# lab10.net
KiCad netlist of a schematic drawn in EAGLE
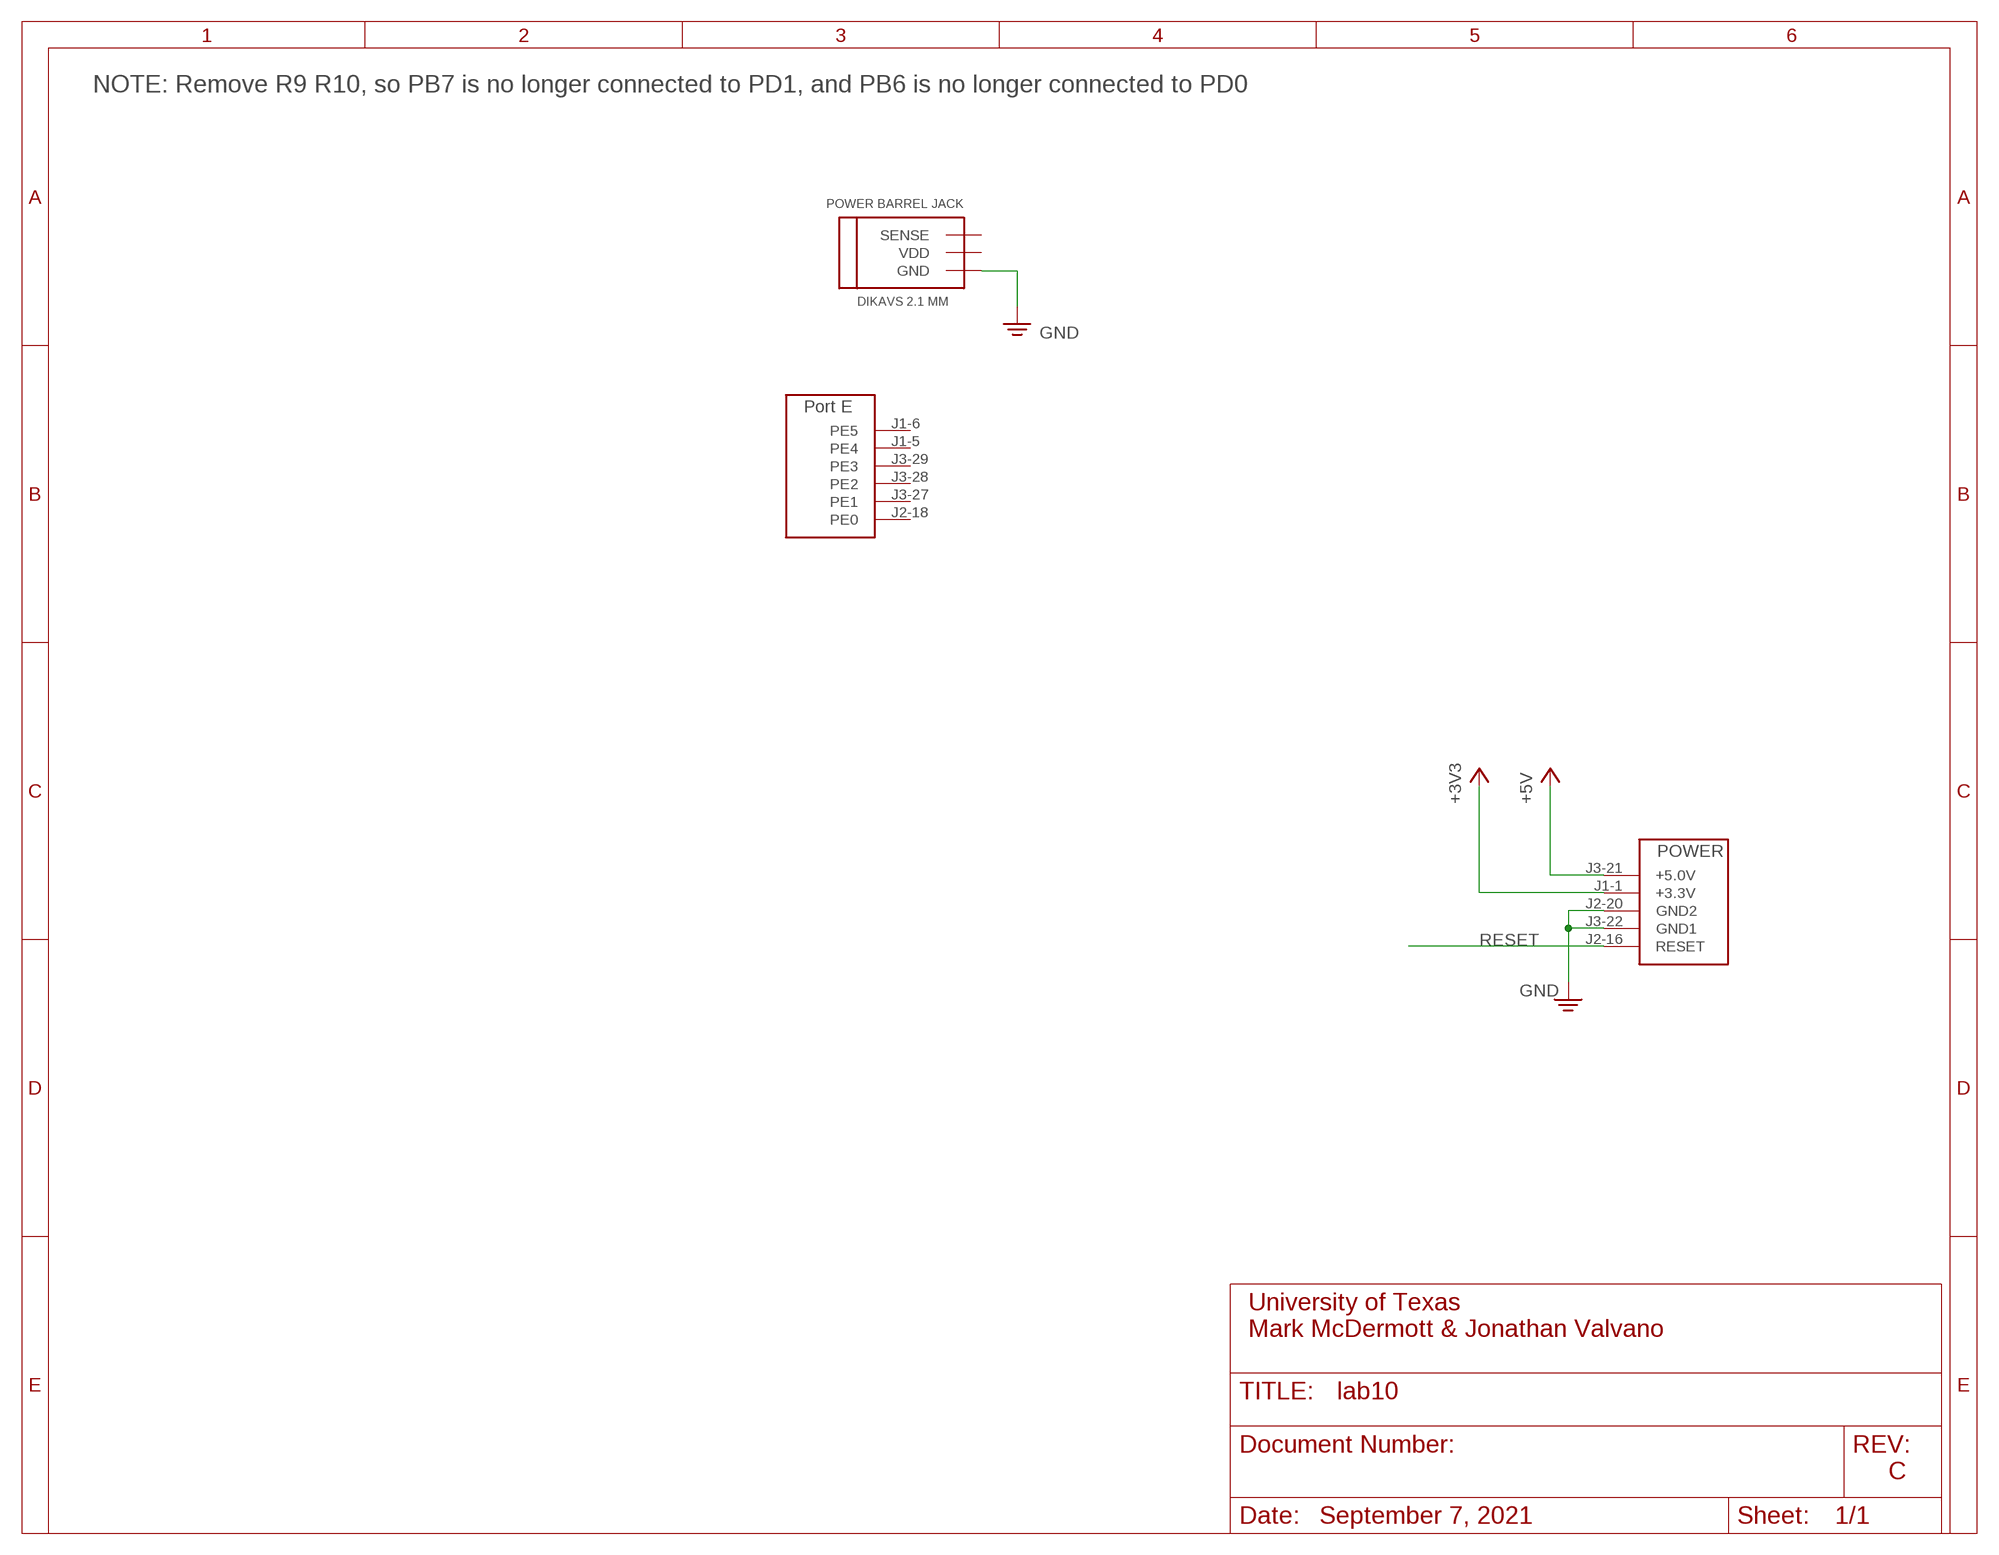
[diagram p0: schematic, sheet 1, part 1 of 2]
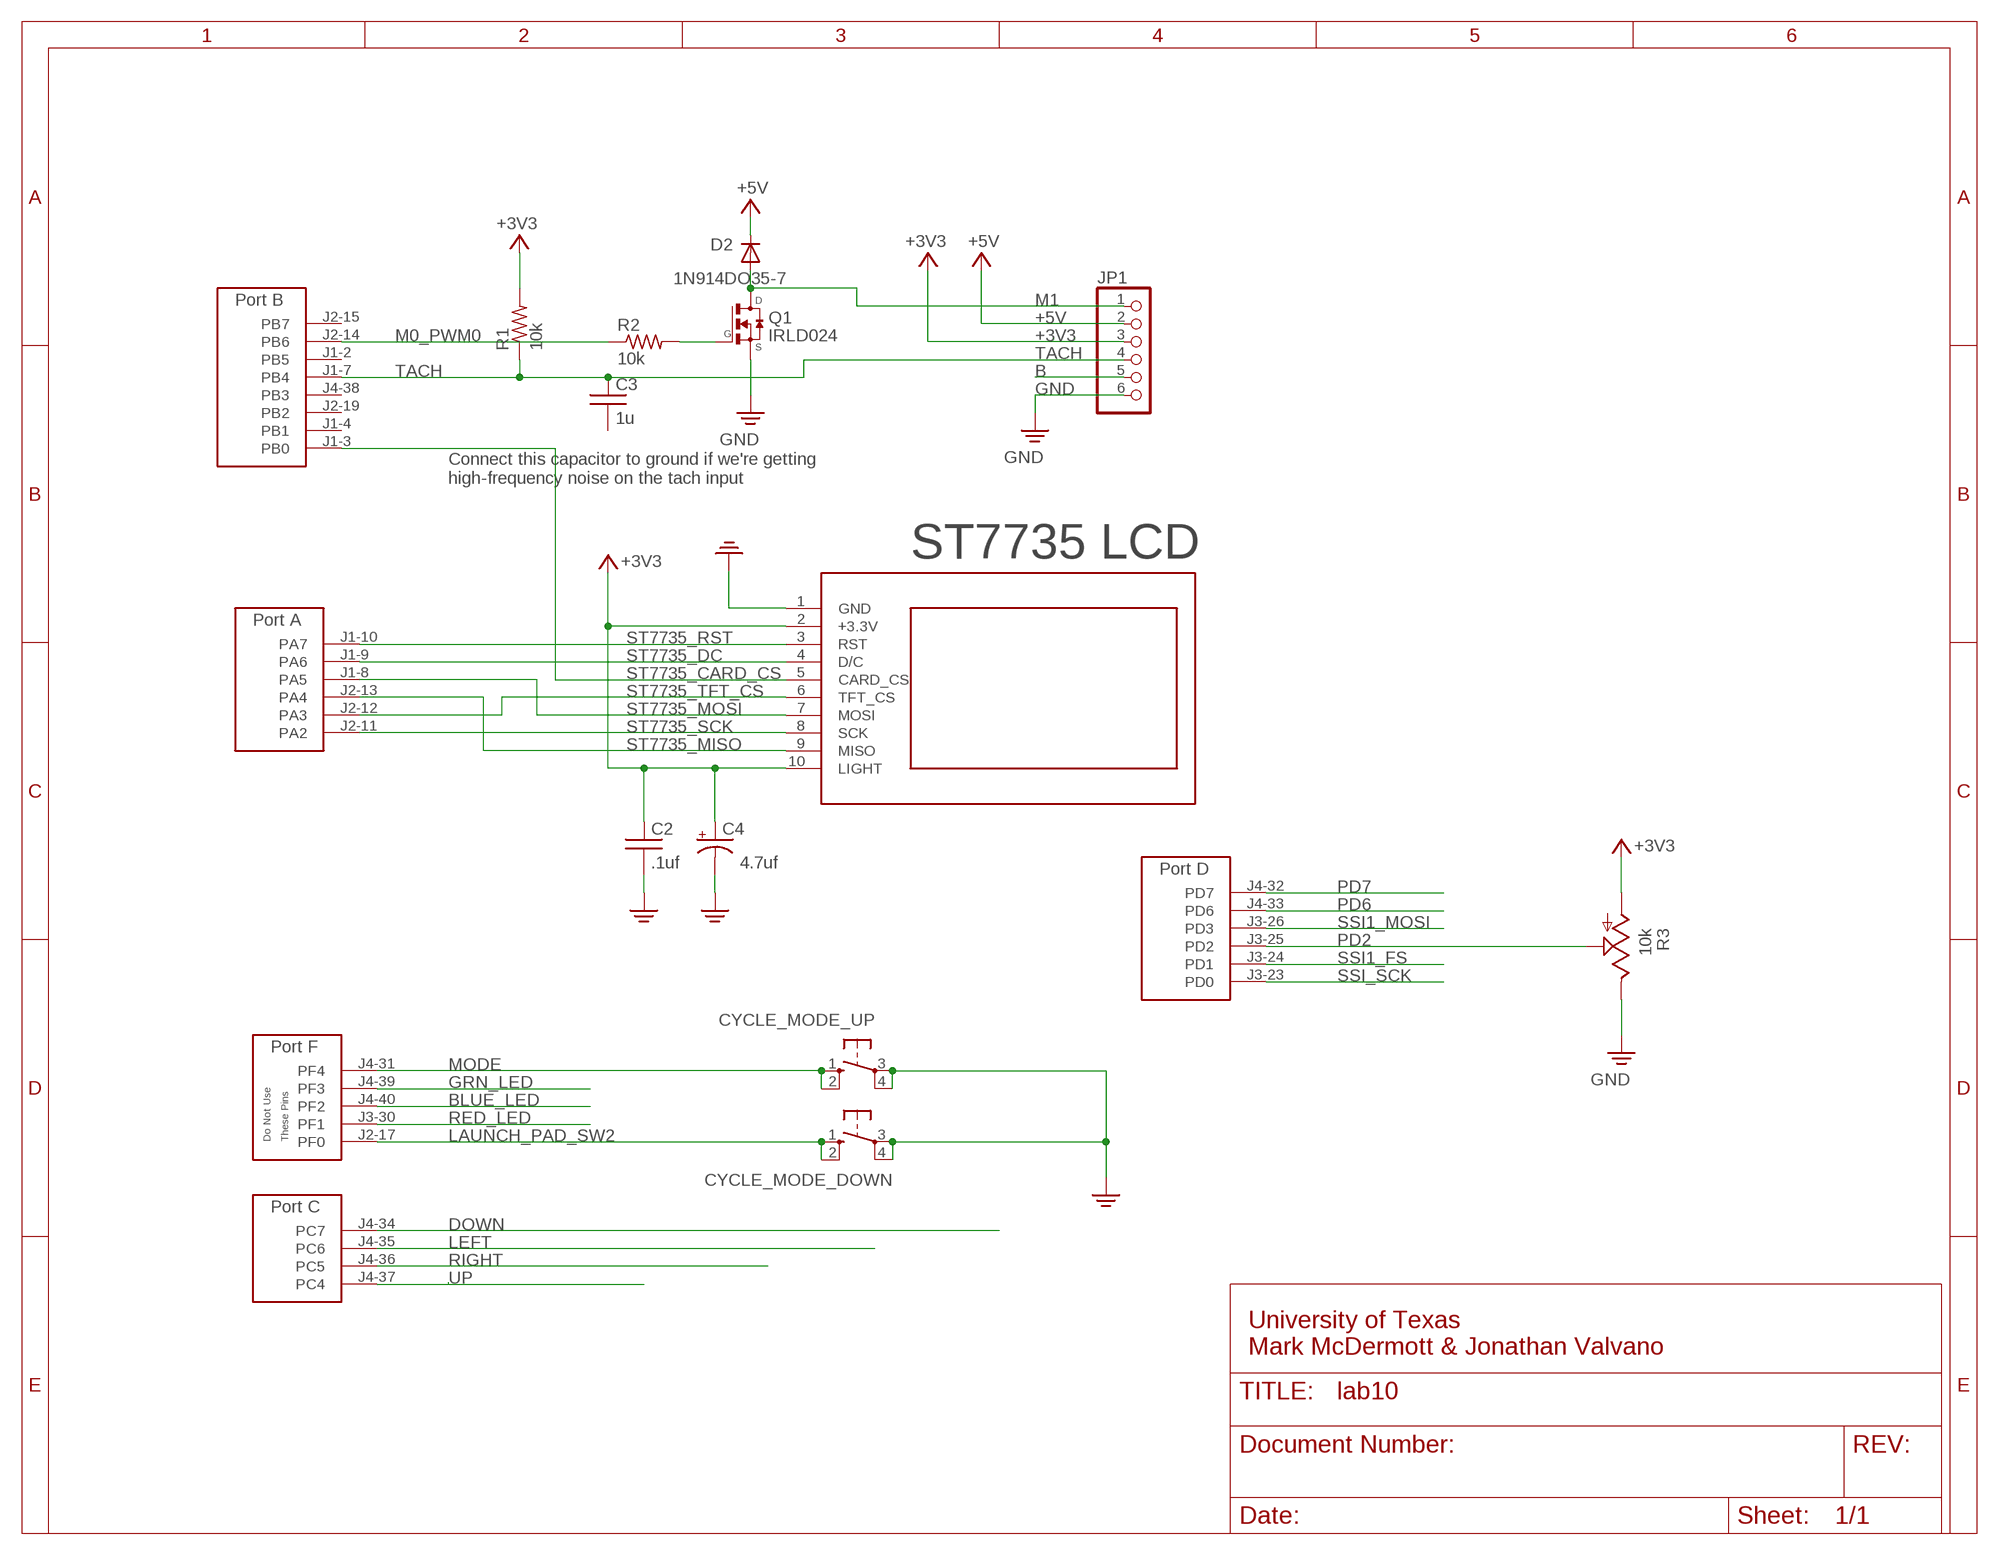
[diagram p1: schematic, sheet 1, part 2 of 2]

(export (version "E")
  (design (tool "Eeschema 10.0.6"))
  (components
    (comp (ref "C2")
      (value ".1uf")
      (footprint "eagle-import:CAP200MIL")
      (libsource (lib "eagle-import") (part "CAPACITOR050-024X044"))
    )
    (comp (ref "C3")
      (value "1u")
      (footprint "eagle-import:CAP100MIL")
      (libsource (lib "eagle-import") (part "EE445L_31078833_CAPACITOR025-024X044"))
    )
    (comp (ref "C4")
      (value "4.7uf")
      (footprint "eagle-import:CAP200MILPOLARIZED")
      (libsource (lib "eagle-import") (part "CAPACITOR_POLARIZEDE5-6"))
    )
    (comp (ref "CYCLE_MODE_DOWN")
      (value "B3F-1052")
      (footprint "eagle-import:B3F-10XX")
      (fields (field (name "MPN") "B3F-1000"))
      (libsource (lib "eagle-import") (part "B3F-1052"))
    )
    (comp (ref "CYCLE_MODE_UP")
      (value "B3F-1052")
      (footprint "eagle-import:B3F-10XX")
      (fields (field (name "MPN") "B3F-1000"))
      (libsource (lib "eagle-import") (part "B3F-1052"))
    )
    (comp (ref "D2")
      (value "1N914DO35-7")
      (footprint "eagle-import:DO35-7")
      (libsource (lib "eagle-import") (part "1N914DO35-7"))
    )
    (comp (ref "JP1")
      (value "PINHD-1X6")
      (footprint "eagle-import:1X06")
      (libsource (lib "eagle-import") (part "PINHD-1X6"))
    )
    (comp (ref "Q1")
      (value "IRLD024")
      (footprint "eagle-import:IRLD024")
      (libsource (lib "eagle-import") (part "IRLD024"))
    )
    (comp (ref "R1")
      (value "10k")
      (footprint "eagle-import:RES300MIL")
      (libsource (lib "eagle-import") (part "RESISTOR0204/7"))
    )
    (comp (ref "R2")
      (value "10k")
      (footprint "eagle-import:RES300MIL")
      (libsource (lib "eagle-import") (part "RESISTOR0204/7"))
    )
    (comp (ref "R3")
      (value "10k")
      (footprint "eagle-import:PTA2043")
      (libsource (lib "eagle-import") (part "POTENTIOMETER_PTA2043B25U"))
    )
    (comp (ref "U$2")
      (value "TM4C_BP")
      (footprint "eagle-import:TM4C_BOOSTER_PACK")
      (libsource (lib "eagle-import") (part "TM4C_BP"))
    )
    (comp (ref "U$3")
      (value "ST7735")
      (footprint "eagle-import:ST7735")
      (libsource (lib "eagle-import") (part "ST7735"))
    )
    (comp (ref "U$4")
      (value "2.1MM_BARREL_JACK")
      (footprint "eagle-import:2.1M_BARREL_JACK")
      (libsource (lib "eagle-import") (part "2.1MM_BARREL_JACK"))
    )
  )
  (nets
    (net (code "1") (name "+3V3") (class "Default")
      (node (ref "C2") (pin "1") (pinfunction "1_1") (pintype "passive"))
      (node (ref "C4") (pin "+") (pinfunction "+_+") (pintype "passive"))
      (node (ref "JP1") (pin "3") (pinfunction "3_3") (pintype "passive"))
      (node (ref "R1") (pin "2") (pinfunction "2_2") (pintype "passive"))
      (node (ref "R3") (pin "3") (pinfunction "A_3") (pintype "passive"))
      (node (ref "U$2") (pin "J1-1") (pinfunction "+3.3V_J1-1") (pintype "bidirectional"))
      (node (ref "U$3") (pin "10") (pinfunction "LIGHT_10") (pintype "bidirectional"))
      (node (ref "U$3") (pin "2") (pinfunction "+3.3V_2") (pintype "bidirectional"))
    )
    (net (code "2") (name "+5V") (class "Default")
      (node (ref "D2") (pin "C") (pinfunction "C_C") (pintype "passive"))
      (node (ref "JP1") (pin "2") (pinfunction "2_2") (pintype "passive"))
      (node (ref "U$2") (pin "J3-21") (pinfunction "+5.0V_J3-21") (pintype "bidirectional"))
    )
    (net (code "3") (name "/B") (class "Default")
      (node (ref "JP1") (pin "5") (pinfunction "5_5") (pintype "passive"))
    )
    (net (code "4") (name "/BLUE_LED") (class "Default")
      (node (ref "U$2") (pin "J4-40") (pinfunction "PF2_J4-40") (pintype "bidirectional"))
    )
    (net (code "5") (name "/DOWN") (class "Default")
      (node (ref "U$2") (pin "J4-34") (pinfunction "PC7_J4-34") (pintype "bidirectional"))
    )
    (net (code "6") (name "/GRN_LED") (class "Default")
      (node (ref "U$2") (pin "J4-39") (pinfunction "PF3_J4-39") (pintype "bidirectional"))
    )
    (net (code "7") (name "/LAUNCH_PAD_SW2") (class "Default")
      (node (ref "CYCLE_MODE_DOWN") (pin "1") (pinfunction "S_1") (pintype "passive"))
      (node (ref "CYCLE_MODE_DOWN") (pin "2") (pinfunction "S1_2") (pintype "passive"))
      (node (ref "U$2") (pin "J2-17") (pinfunction "PF0_J2-17") (pintype "bidirectional"))
    )
    (net (code "8") (name "/LEFT") (class "Default")
      (node (ref "U$2") (pin "J4-35") (pinfunction "PC6_J4-35") (pintype "bidirectional"))
    )
    (net (code "9") (name "/M0_PWM0") (class "Default")
      (node (ref "R2") (pin "1") (pinfunction "1_1") (pintype "passive"))
      (node (ref "U$2") (pin "J2-14") (pinfunction "PB6_J2-14") (pintype "bidirectional"))
    )
    (net (code "10") (name "/M1") (class "Default")
      (node (ref "D2") (pin "A") (pinfunction "A_A") (pintype "passive"))
      (node (ref "JP1") (pin "1") (pinfunction "1_1") (pintype "passive"))
      (node (ref "Q1") (pin "P$1") (pinfunction "D_P$1") (pintype "passive"))
    )
    (net (code "11") (name "/MODE") (class "Default")
      (node (ref "CYCLE_MODE_UP") (pin "1") (pinfunction "S_1") (pintype "passive"))
      (node (ref "CYCLE_MODE_UP") (pin "2") (pinfunction "S1_2") (pintype "passive"))
      (node (ref "U$2") (pin "J4-31") (pinfunction "PF4_J4-31") (pintype "bidirectional"))
    )
    (net (code "12") (name "/PD2") (class "Default")
      (node (ref "R3") (pin "2") (pinfunction "S_2") (pintype "passive"))
      (node (ref "U$2") (pin "J3-25") (pinfunction "PD2_J3-25") (pintype "bidirectional"))
    )
    (net (code "13") (name "/PD6") (class "Default")
      (node (ref "U$2") (pin "J4-33") (pinfunction "PD6_J4-33") (pintype "bidirectional"))
    )
    (net (code "14") (name "/PD7") (class "Default")
      (node (ref "U$2") (pin "J4-32") (pinfunction "PD7_J4-32") (pintype "bidirectional"))
    )
    (net (code "15") (name "/RED_LED") (class "Default")
      (node (ref "U$2") (pin "J3-30") (pinfunction "PF1_J3-30") (pintype "bidirectional"))
    )
    (net (code "16") (name "/RESET") (class "Default")
      (node (ref "U$2") (pin "J2-16") (pinfunction "RESET_J2-16") (pintype "bidirectional"))
    )
    (net (code "17") (name "/RIGHT") (class "Default")
      (node (ref "U$2") (pin "J4-36") (pinfunction "PC5_J4-36") (pintype "bidirectional"))
    )
    (net (code "18") (name "/SSI1_FS") (class "Default")
      (node (ref "U$2") (pin "J3-24") (pinfunction "PD1_J3-24") (pintype "bidirectional"))
    )
    (net (code "19") (name "/SSI1_MOSI") (class "Default")
      (node (ref "U$2") (pin "J3-26") (pinfunction "PD3_J3-26") (pintype "bidirectional"))
    )
    (net (code "20") (name "/SSI_SCK") (class "Default")
      (node (ref "U$2") (pin "J3-23") (pinfunction "PD0_J3-23") (pintype "bidirectional"))
    )
    (net (code "21") (name "/ST7735_CARD_CS") (class "Default")
      (node (ref "U$2") (pin "J1-3") (pinfunction "PB0_J1-3") (pintype "bidirectional"))
      (node (ref "U$3") (pin "5") (pinfunction "CARD_CS_5") (pintype "bidirectional"))
    )
    (net (code "22") (name "/ST7735_DC") (class "Default")
      (node (ref "U$2") (pin "J1-9") (pinfunction "PA6_J1-9") (pintype "bidirectional"))
      (node (ref "U$3") (pin "4") (pinfunction "D/C_4") (pintype "bidirectional"))
    )
    (net (code "23") (name "/ST7735_MISO") (class "Default")
      (node (ref "U$2") (pin "J2-13") (pinfunction "PA4_J2-13") (pintype "bidirectional"))
      (node (ref "U$3") (pin "9") (pinfunction "MISO_9") (pintype "bidirectional"))
    )
    (net (code "24") (name "/ST7735_MOSI") (class "Default")
      (node (ref "U$2") (pin "J1-8") (pinfunction "PA5_J1-8") (pintype "bidirectional"))
      (node (ref "U$3") (pin "7") (pinfunction "MOSI_7") (pintype "bidirectional"))
    )
    (net (code "25") (name "/ST7735_RST") (class "Default")
      (node (ref "U$2") (pin "J1-10") (pinfunction "PA7_J1-10") (pintype "bidirectional"))
      (node (ref "U$3") (pin "3") (pinfunction "RST_3") (pintype "bidirectional"))
    )
    (net (code "26") (name "/ST7735_SCK") (class "Default")
      (node (ref "U$2") (pin "J2-11") (pinfunction "PA2_J2-11") (pintype "bidirectional"))
      (node (ref "U$3") (pin "8") (pinfunction "SCK_8") (pintype "bidirectional"))
    )
    (net (code "27") (name "/ST7735_TFT_CS") (class "Default")
      (node (ref "U$2") (pin "J2-12") (pinfunction "PA3_J2-12") (pintype "bidirectional"))
      (node (ref "U$3") (pin "6") (pinfunction "TFT_CS_6") (pintype "bidirectional"))
    )
    (net (code "28") (name "/TACH") (class "Default")
      (node (ref "C3") (pin "1") (pinfunction "1_1") (pintype "passive"))
      (node (ref "JP1") (pin "4") (pinfunction "4_4") (pintype "passive"))
      (node (ref "R1") (pin "1") (pinfunction "1_1") (pintype "passive"))
      (node (ref "U$2") (pin "J1-7") (pinfunction "PB4_J1-7") (pintype "bidirectional"))
    )
    (net (code "29") (name "/UP") (class "Default")
      (node (ref "U$2") (pin "J4-37") (pinfunction "PC4_J4-37") (pintype "bidirectional"))
    )
    (net (code "30") (name "GND") (class "Default")
      (node (ref "C2") (pin "2") (pinfunction "2_2") (pintype "passive"))
      (node (ref "C4") (pin "-") (pinfunction "-_-") (pintype "passive"))
      (node (ref "CYCLE_MODE_DOWN") (pin "3") (pinfunction "P_3") (pintype "passive"))
      (node (ref "CYCLE_MODE_DOWN") (pin "4") (pinfunction "P1_4") (pintype "passive"))
      (node (ref "CYCLE_MODE_UP") (pin "3") (pinfunction "P_3") (pintype "passive"))
      (node (ref "CYCLE_MODE_UP") (pin "4") (pinfunction "P1_4") (pintype "passive"))
      (node (ref "JP1") (pin "6") (pinfunction "6_6") (pintype "passive"))
      (node (ref "Q1") (pin "P$4") (pinfunction "S_P$4") (pintype "passive"))
      (node (ref "R3") (pin "1") (pinfunction "E_1") (pintype "passive"))
      (node (ref "U$2") (pin "J2-20") (pinfunction "GND2_J2-20") (pintype "bidirectional"))
      (node (ref "U$2") (pin "J3-22") (pinfunction "GND1_J3-22") (pintype "bidirectional"))
      (node (ref "U$3") (pin "1") (pinfunction "GND_1") (pintype "bidirectional"))
      (node (ref "U$4") (pin "GND") (pinfunction "GND_GND") (pintype "bidirectional"))
    )
    (net (code "31") (name "Net-(Q1-G)") (class "Default")
      (node (ref "Q1") (pin "P$3") (pinfunction "G_P$3") (pintype "passive"))
      (node (ref "R2") (pin "2") (pinfunction "2_2") (pintype "passive"))
    )
    (net (code "32") (name "unconnected-(C3-Pad2)") (class "Default")
      (node (ref "C3") (pin "2") (pinfunction "2_2") (pintype "passive"))
    )
    (net (code "33") (name "unconnected-(U$2B-PB1-PadJ1-4)") (class "Default")
      (node (ref "U$2") (pin "J1-4") (pinfunction "PB1_J1-4") (pintype "bidirectional"))
    )
    (net (code "34") (name "unconnected-(U$2B-PB2-PadJ2-19)") (class "Default")
      (node (ref "U$2") (pin "J2-19") (pinfunction "PB2_J2-19") (pintype "bidirectional"))
    )
    (net (code "35") (name "unconnected-(U$2B-PB3-PadJ4-38)") (class "Default")
      (node (ref "U$2") (pin "J4-38") (pinfunction "PB3_J4-38") (pintype "bidirectional"))
    )
    (net (code "36") (name "unconnected-(U$2B-PB5-PadJ1-2)") (class "Default")
      (node (ref "U$2") (pin "J1-2") (pinfunction "PB5_J1-2") (pintype "bidirectional"))
    )
    (net (code "37") (name "unconnected-(U$2B-PB7-PadJ2-15)") (class "Default")
      (node (ref "U$2") (pin "J2-15") (pinfunction "PB7_J2-15") (pintype "bidirectional"))
    )
    (net (code "38") (name "unconnected-(U$2E-PE0-PadJ2-18)") (class "Default")
      (node (ref "U$2") (pin "J2-18") (pinfunction "PE0_J2-18") (pintype "bidirectional"))
    )
    (net (code "39") (name "unconnected-(U$2E-PE1-PadJ3-27)") (class "Default")
      (node (ref "U$2") (pin "J3-27") (pinfunction "PE1_J3-27") (pintype "bidirectional"))
    )
    (net (code "40") (name "unconnected-(U$2E-PE2-PadJ3-28)") (class "Default")
      (node (ref "U$2") (pin "J3-28") (pinfunction "PE2_J3-28") (pintype "bidirectional"))
    )
    (net (code "41") (name "unconnected-(U$2E-PE3-PadJ3-29)") (class "Default")
      (node (ref "U$2") (pin "J3-29") (pinfunction "PE3_J3-29") (pintype "bidirectional"))
    )
    (net (code "42") (name "unconnected-(U$2E-PE4-PadJ1-5)") (class "Default")
      (node (ref "U$2") (pin "J1-5") (pinfunction "PE4_J1-5") (pintype "bidirectional"))
    )
    (net (code "43") (name "unconnected-(U$2E-PE5-PadJ1-6)") (class "Default")
      (node (ref "U$2") (pin "J1-6") (pinfunction "PE5_J1-6") (pintype "bidirectional"))
    )
    (net (code "44") (name "unconnected-(U$4-PadSENSE)") (class "Default")
      (node (ref "U$4") (pin "SENSE") (pinfunction "SENSE_SENSE") (pintype "bidirectional"))
    )
    (net (code "45") (name "unconnected-(U$4-PadVDD)") (class "Default")
      (node (ref "U$4") (pin "VDD") (pinfunction "VDD_VDD") (pintype "bidirectional"))
    )
  )
)
